# DOut_Relay.net
KiCad netlist of a schematic drawn in Altium Designer
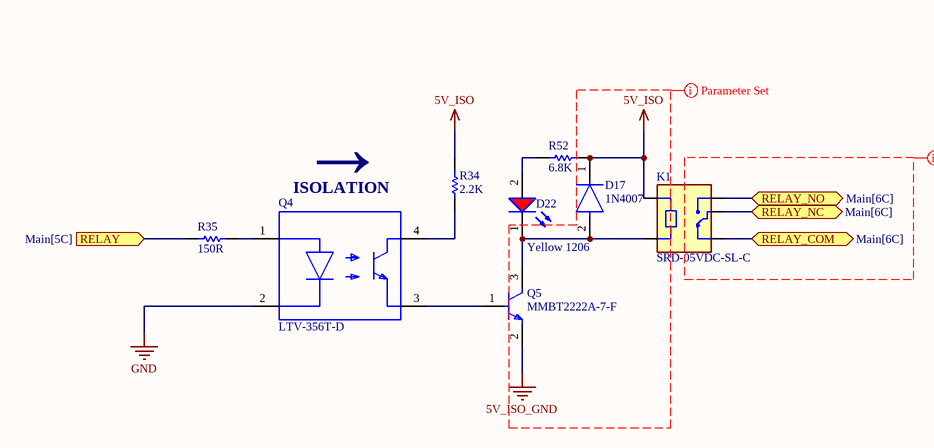
[diagram p0: DOut_Relay.SchDoc]

(export (version "E")
  (design (tool "Eeschema 10.0.6"))
  (components
    (comp (ref "D17")
      (value "1N4007")
      (footprint "FP-1N4007_SMD-IPC_C")
      (description "Rectifier, 1Kv, 1A, Do-214Ac Rohs Compliant: Yes")
      (libsource (lib "Altium Content Vault") (part "d7152d700b627762746794eb795d46e"))
    )
    (comp (ref "D22")
      (value "Yellow 1206")
      (footprint "WL-SMCW_1206_150120xx75000")
      (description "Led, Red, 630 Nm, 1.9 V, 30 Ma, 60 Mcd Rohs Compliant: Yes")
      (libsource (lib "Altium Content Vault") (part "LED_Red_2A-1K"))
    )
    (comp (ref "K1")
      (value "SRD-05VDC-SL-C")
      (footprint "RELAY_SRD-05VDC-SL-C")
      (fields (field (name "MF") "Songle Relay"))
      (libsource (lib "SRD-05VDC-SL-C") (part "SRD-05VDC-SL-C"))
    )
    (comp (ref "Q4")
      (value "LTV-356T-D")
      (footprint "FP-LTV-356T-D-MFG")
      (description "OPTOCPL 1 CH TRAN OUT SMT")
      (fields
        (field (name "MANUFACTURER") "Lite-On")
        (field (name "OCTOPART") "https://octopart.com/ltv-356t-d-lite-on-11764243")
      )
      (libsource (lib "Altium Content Vault") (part "34aec040319b23b6d7df8c049769266"))
    )
    (comp (ref "Q5")
      (value "MMBT2222A-7-F")
      (footprint "FP-SOT23-IPC_A")
      (description "TRANS NPN 40V 0.6A SMD SOT23-3")
      (fields (field (name "VOLTAGE") "40V"))
      (libsource (lib "Altium Content Vault") (part "b44e953556f554d0102664c7d152cb4"))
    )
    (comp (ref "R34")
      (value "2.2K")
      (footprint "RESC1608X55X30LL15T15")
      (fields (field (name "PART NUMBER") "ERJ3EKF2201V") (field (name "MANUFACTURER") "Panasonic"))
      (libsource (lib "Altium Content Vault") (part "RES"))
    )
    (comp (ref "R35")
      (value "150R")
      (footprint "RESC1608X55X30ML20T20")
      (fields (field (name "PART NUMBER") "ERA3AEB151V") (field (name "MANUFACTURER") "Panasonic"))
      (libsource (lib "Altium Content Vault") (part "RES"))
    )
    (comp (ref "R52")
      (value "6.8K")
      (footprint "RESC1608X55X30LL15T15")
      (fields (field (name "PART NUMBER") "ERJ-3GEYJ512V") (field (name "MANUFACTURER") "Panasonic"))
      (libsource (lib "Altium Content Vault") (part "RES"))
    )
  )
  (nets
    (net (code "1") (name "/RELAY") (class "Default")
      (node (ref "R35") (pin "1") (pinfunction "1_1") (pintype "passive"))
    )
    (net (code "2") (name "/RELAY_COM") (class "Default")
      (node (ref "K1") (pin "NC") (pinfunction "NC_NC") (pintype "passive"))
    )
    (net (code "3") (name "/RELAY_NC") (class "Default")
      (node (ref "K1") (pin "COM") (pinfunction "COM_COM") (pintype "passive"))
    )
    (net (code "4") (name "/RELAY_NO") (class "Default")
      (node (ref "K1") (pin "NO") (pinfunction "NO_NO") (pintype "passive"))
    )
    (net (code "5") (name "5V_ISO") (class "Default")
      (node (ref "D17") (pin "1") (pinfunction "C_1") (pintype "passive"))
      (node (ref "K1") (pin "A1") (pinfunction "A1_A1") (pintype "passive"))
      (node (ref "R34") (pin "1") (pinfunction "1_1") (pintype "passive"))
      (node (ref "R52") (pin "2") (pinfunction "2_2") (pintype "passive"))
    )
    (net (code "6") (name "5V_ISO_GND") (class "Default")
      (node (ref "Q5") (pin "2") (pinfunction "E_2") (pintype "passive"))
    )
    (net (code "7") (name "GND") (class "Default")
      (node (ref "Q4") (pin "2") (pinfunction "C_2") (pintype "passive"))
    )
    (net (code "8") (name "Net-(D17-A)") (class "Default")
      (node (ref "D17") (pin "2") (pinfunction "A_2") (pintype "passive"))
      (node (ref "D22") (pin "1") (pinfunction "K_1") (pintype "passive"))
      (node (ref "K1") (pin "A2") (pinfunction "A2_A2") (pintype "passive"))
      (node (ref "Q5") (pin "3") (pinfunction "C_3") (pintype "passive"))
    )
    (net (code "9") (name "Net-(D22-A)") (class "Default")
      (node (ref "D22") (pin "2") (pinfunction "A_2") (pintype "passive"))
      (node (ref "R52") (pin "1") (pinfunction "1_1") (pintype "passive"))
    )
    (net (code "10") (name "Net-(Q4-A)") (class "Default")
      (node (ref "Q4") (pin "1") (pinfunction "A_1") (pintype "passive"))
      (node (ref "R35") (pin "2") (pinfunction "2_2") (pintype "passive"))
    )
    (net (code "11") (name "Net-(Q4-C-Pad4)") (class "Default")
      (node (ref "Q4") (pin "4") (pinfunction "C_4") (pintype "passive"))
      (node (ref "R34") (pin "2") (pinfunction "2_2") (pintype "passive"))
    )
    (net (code "12") (name "Net-(Q4-E)") (class "Default")
      (node (ref "Q4") (pin "3") (pinfunction "E_3") (pintype "passive"))
      (node (ref "Q5") (pin "1") (pinfunction "B_1") (pintype "passive"))
    )
  )
)
